# Gambar_Teknik_2__Raihansyah_Akbar_M__215.net
KiCad netlist of a schematic drawn in EAGLE
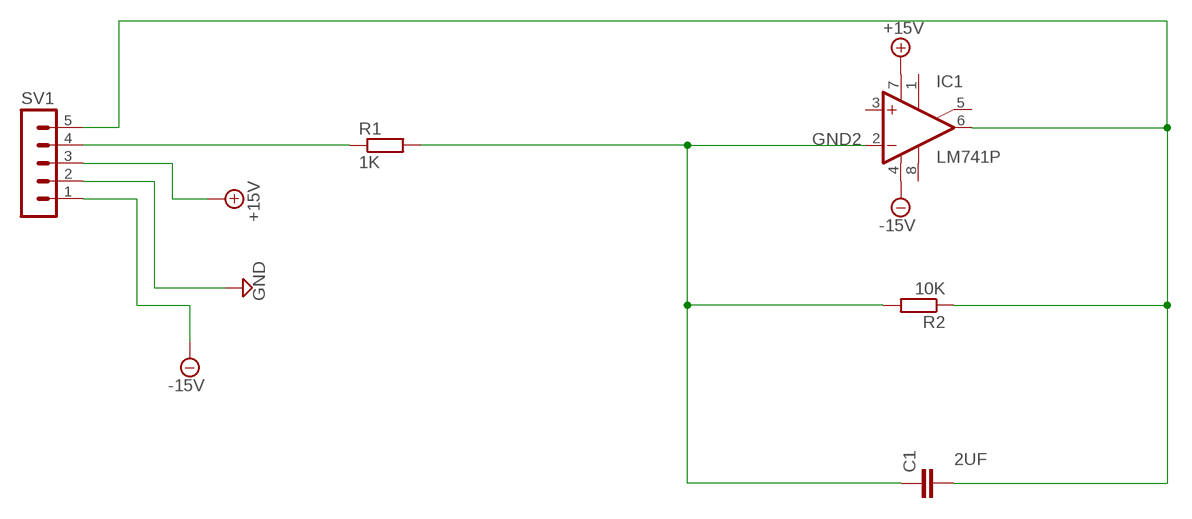
[diagram p0: schematic, sheet 1]

(export (version "E")
  (design (tool "Eeschema 10.0.6"))
  (components
    (comp (ref "C1")
      (value "C-EU025-024X044")
      (footprint "eagle-import:C025-024X044")
      (libsource (lib "eagle-import") (part "C-EU025-024X044"))
    )
    (comp (ref "IC1")
      (value "LM741P")
      (footprint "eagle-import:DIL08")
      (libsource (lib "eagle-import") (part "741PLM"))
    )
    (comp (ref "R1")
      (value "1K")
      (footprint "eagle-import:0204V")
      (libsource (lib "eagle-import") (part "R-EU_0204/2V"))
    )
    (comp (ref "R2")
      (value "10K")
      (footprint "eagle-import:0204V")
      (libsource (lib "eagle-import") (part "R-EU_0204/2V"))
    )
    (comp (ref "SV1")
      (value "MA05-1")
      (footprint "eagle-import:MA05-1")
      (libsource (lib "eagle-import") (part "MA05-1"))
    )
  )
  (nets
    (net (code "1") (name "+15V") (class "Default")
      (node (ref "IC1") (pin "7") (pinfunction "V+_7") (pintype "power_in"))
      (node (ref "SV1") (pin "3") (pinfunction "3_3") (pintype "passive"))
    )
    (net (code "2") (name "-15V") (class "Default")
      (node (ref "IC1") (pin "4") (pinfunction "V-_4") (pintype "power_in"))
      (node (ref "SV1") (pin "1") (pinfunction "1_1") (pintype "passive"))
    )
    (net (code "3") (name "/2UF") (class "Default")
      (node (ref "C1") (pin "2") (pinfunction "2_2") (pintype "passive"))
      (node (ref "IC1") (pin "6") (pinfunction "OUT_6") (pintype "output"))
      (node (ref "R2") (pin "1") (pinfunction "1_1") (pintype "passive"))
      (node (ref "SV1") (pin "5") (pinfunction "5_5") (pintype "passive"))
    )
    (net (code "4") (name "/GND2") (class "Default")
      (node (ref "C1") (pin "1") (pinfunction "1_1") (pintype "passive"))
      (node (ref "IC1") (pin "2") (pinfunction "-IN_2") (pintype "input"))
      (node (ref "R1") (pin "2") (pinfunction "2_2") (pintype "passive"))
      (node (ref "R2") (pin "2") (pinfunction "2_2") (pintype "passive"))
    )
    (net (code "5") (name "GND") (class "Default")
      (node (ref "SV1") (pin "2") (pinfunction "2_2") (pintype "passive"))
    )
    (net (code "6") (name "Net-(R1-Pad1)") (class "Default")
      (node (ref "R1") (pin "1") (pinfunction "1_1") (pintype "passive"))
      (node (ref "SV1") (pin "4") (pinfunction "4_4") (pintype "passive"))
    )
    (net (code "7") (name "unconnected-(IC1-+IN-Pad3)") (class "Default")
      (node (ref "IC1") (pin "3") (pinfunction "+IN_3") (pintype "input"))
    )
    (net (code "8") (name "unconnected-(IC1-ON1-Pad1)") (class "Default")
      (node (ref "IC1") (pin "1") (pinfunction "ON1_1") (pintype "passive"))
    )
    (net (code "9") (name "unconnected-(IC1-ON2-Pad5)") (class "Default")
      (node (ref "IC1") (pin "5") (pinfunction "ON2_5") (pintype "passive"))
    )
    (net (code "10") (name "unconnected-(IC1-OPT-Pad8)") (class "Default")
      (node (ref "IC1") (pin "8") (pinfunction "OPT_8") (pintype "passive"))
    )
  )
)
